# Dual_Power_Supply.net
KiCad netlist of a schematic drawn in EAGLE
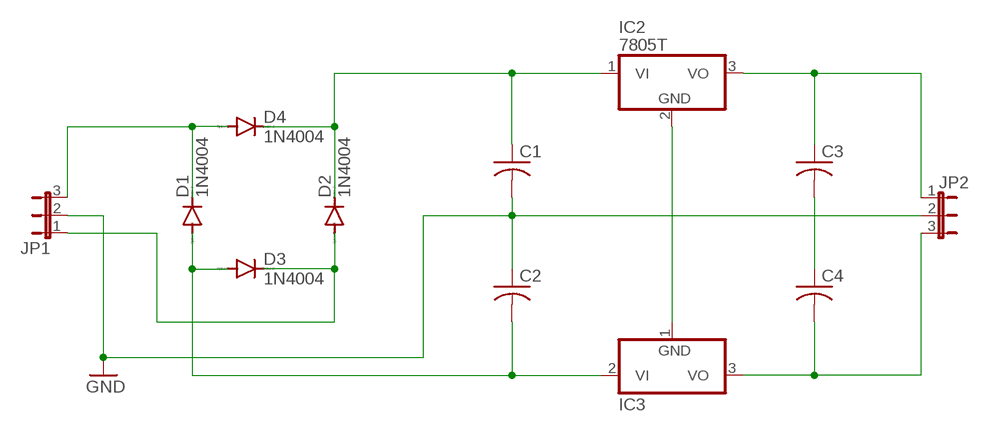
[diagram p0: schematic, sheet 1]

(export (version "E")
  (design (tool "Eeschema 10.0.6"))
  (components
    (comp (ref "C1")
      (value "C-US025-025X050")
      (footprint "eagle-import:C025-025X050")
      (libsource (lib "eagle-import") (part "C-US025-025X050"))
    )
    (comp (ref "C2")
      (value "C-US025-025X050")
      (footprint "eagle-import:C025-025X050")
      (libsource (lib "eagle-import") (part "C-US025-025X050"))
    )
    (comp (ref "C3")
      (value "C-US025-025X050")
      (footprint "eagle-import:C025-025X050")
      (libsource (lib "eagle-import") (part "C-US025-025X050"))
    )
    (comp (ref "C4")
      (value "C-US025-025X050")
      (footprint "eagle-import:C025-025X050")
      (libsource (lib "eagle-import") (part "C-US025-025X050"))
    )
    (comp (ref "D1")
      (value "1N4004")
      (footprint "eagle-import:DO41-10")
      (libsource (lib "eagle-import") (part "1N4004"))
    )
    (comp (ref "D2")
      (value "1N4004")
      (footprint "eagle-import:DO41-10")
      (libsource (lib "eagle-import") (part "1N4004"))
    )
    (comp (ref "D3")
      (value "1N4004")
      (footprint "eagle-import:DO41-10")
      (libsource (lib "eagle-import") (part "1N4004"))
    )
    (comp (ref "D4")
      (value "1N4004")
      (footprint "eagle-import:DO41-10")
      (libsource (lib "eagle-import") (part "1N4004"))
    )
    (comp (ref "IC2")
      (value "7805T")
      (footprint "eagle-import:TO220H")
      (libsource (lib "eagle-import") (part "78T05"))
    )
    (comp (ref "IC3")
      (value "7905T")
      (footprint "eagle-import:TO220H")
      (libsource (lib "eagle-import") (part "79T05"))
    )
    (comp (ref "JP1")
      (value "JP2E")
      (footprint "eagle-import:JP2")
      (libsource (lib "eagle-import") (part "JP2E"))
    )
    (comp (ref "JP2")
      (value "JP2E")
      (footprint "eagle-import:JP2")
      (libsource (lib "eagle-import") (part "JP2E"))
    )
  )
  (nets
    (net (code "1") (name "GND") (class "Default")
      (node (ref "C1") (pin "2") (pinfunction "2_2") (pintype "passive"))
      (node (ref "C2") (pin "1") (pinfunction "1_1") (pintype "passive"))
      (node (ref "JP1") (pin "2") (pinfunction "2_2") (pintype "passive"))
      (node (ref "JP2") (pin "2") (pinfunction "2_2") (pintype "passive"))
    )
    (net (code "2") (name "Net-(C3-Pad2)") (class "Default")
      (node (ref "C3") (pin "2") (pinfunction "2_2") (pintype "passive"))
      (node (ref "C4") (pin "1") (pinfunction "1_1") (pintype "passive"))
    )
    (net (code "3") (name "Net-(D1-PadC)") (class "Default")
      (node (ref "D1") (pin "C") (pinfunction "C_C") (pintype "passive"))
      (node (ref "D4") (pin "A") (pinfunction "A_A") (pintype "passive"))
      (node (ref "JP1") (pin "3") (pinfunction "3_3") (pintype "passive"))
    )
    (net (code "4") (name "Net-(D2-PadA)") (class "Default")
      (node (ref "D2") (pin "A") (pinfunction "A_A") (pintype "passive"))
      (node (ref "D3") (pin "C") (pinfunction "C_C") (pintype "passive"))
      (node (ref "JP1") (pin "1") (pinfunction "1_1") (pintype "passive"))
    )
    (net (code "5") (name "Net-(IC2-GND)") (class "Default")
      (node (ref "IC2") (pin "2") (pinfunction "GND_2") (pintype "passive"))
      (node (ref "IC3") (pin "1") (pinfunction "GND_1") (pintype "passive"))
    )
    (net (code "6") (name "Net-(IC2-VI)") (class "Default")
      (node (ref "C1") (pin "1") (pinfunction "1_1") (pintype "passive"))
      (node (ref "D2") (pin "C") (pinfunction "C_C") (pintype "passive"))
      (node (ref "D4") (pin "C") (pinfunction "C_C") (pintype "passive"))
      (node (ref "IC2") (pin "1") (pinfunction "VI_1") (pintype "input"))
    )
    (net (code "7") (name "Net-(IC2-VO)") (class "Default")
      (node (ref "C3") (pin "1") (pinfunction "1_1") (pintype "passive"))
      (node (ref "IC2") (pin "3") (pinfunction "VO_3") (pintype "passive"))
      (node (ref "JP2") (pin "1") (pinfunction "1_1") (pintype "passive"))
    )
    (net (code "8") (name "Net-(IC3-VI)") (class "Default")
      (node (ref "C2") (pin "2") (pinfunction "2_2") (pintype "passive"))
      (node (ref "D1") (pin "A") (pinfunction "A_A") (pintype "passive"))
      (node (ref "D3") (pin "A") (pinfunction "A_A") (pintype "passive"))
      (node (ref "IC3") (pin "2") (pinfunction "VI_2") (pintype "input"))
    )
    (net (code "9") (name "Net-(IC3-VO)") (class "Default")
      (node (ref "C4") (pin "2") (pinfunction "2_2") (pintype "passive"))
      (node (ref "IC3") (pin "3") (pinfunction "VO_3") (pintype "passive"))
      (node (ref "JP2") (pin "3") (pinfunction "3_3") (pintype "passive"))
    )
  )
)
